# goofylite.net
KiCad netlist of a schematic drawn in EAGLE
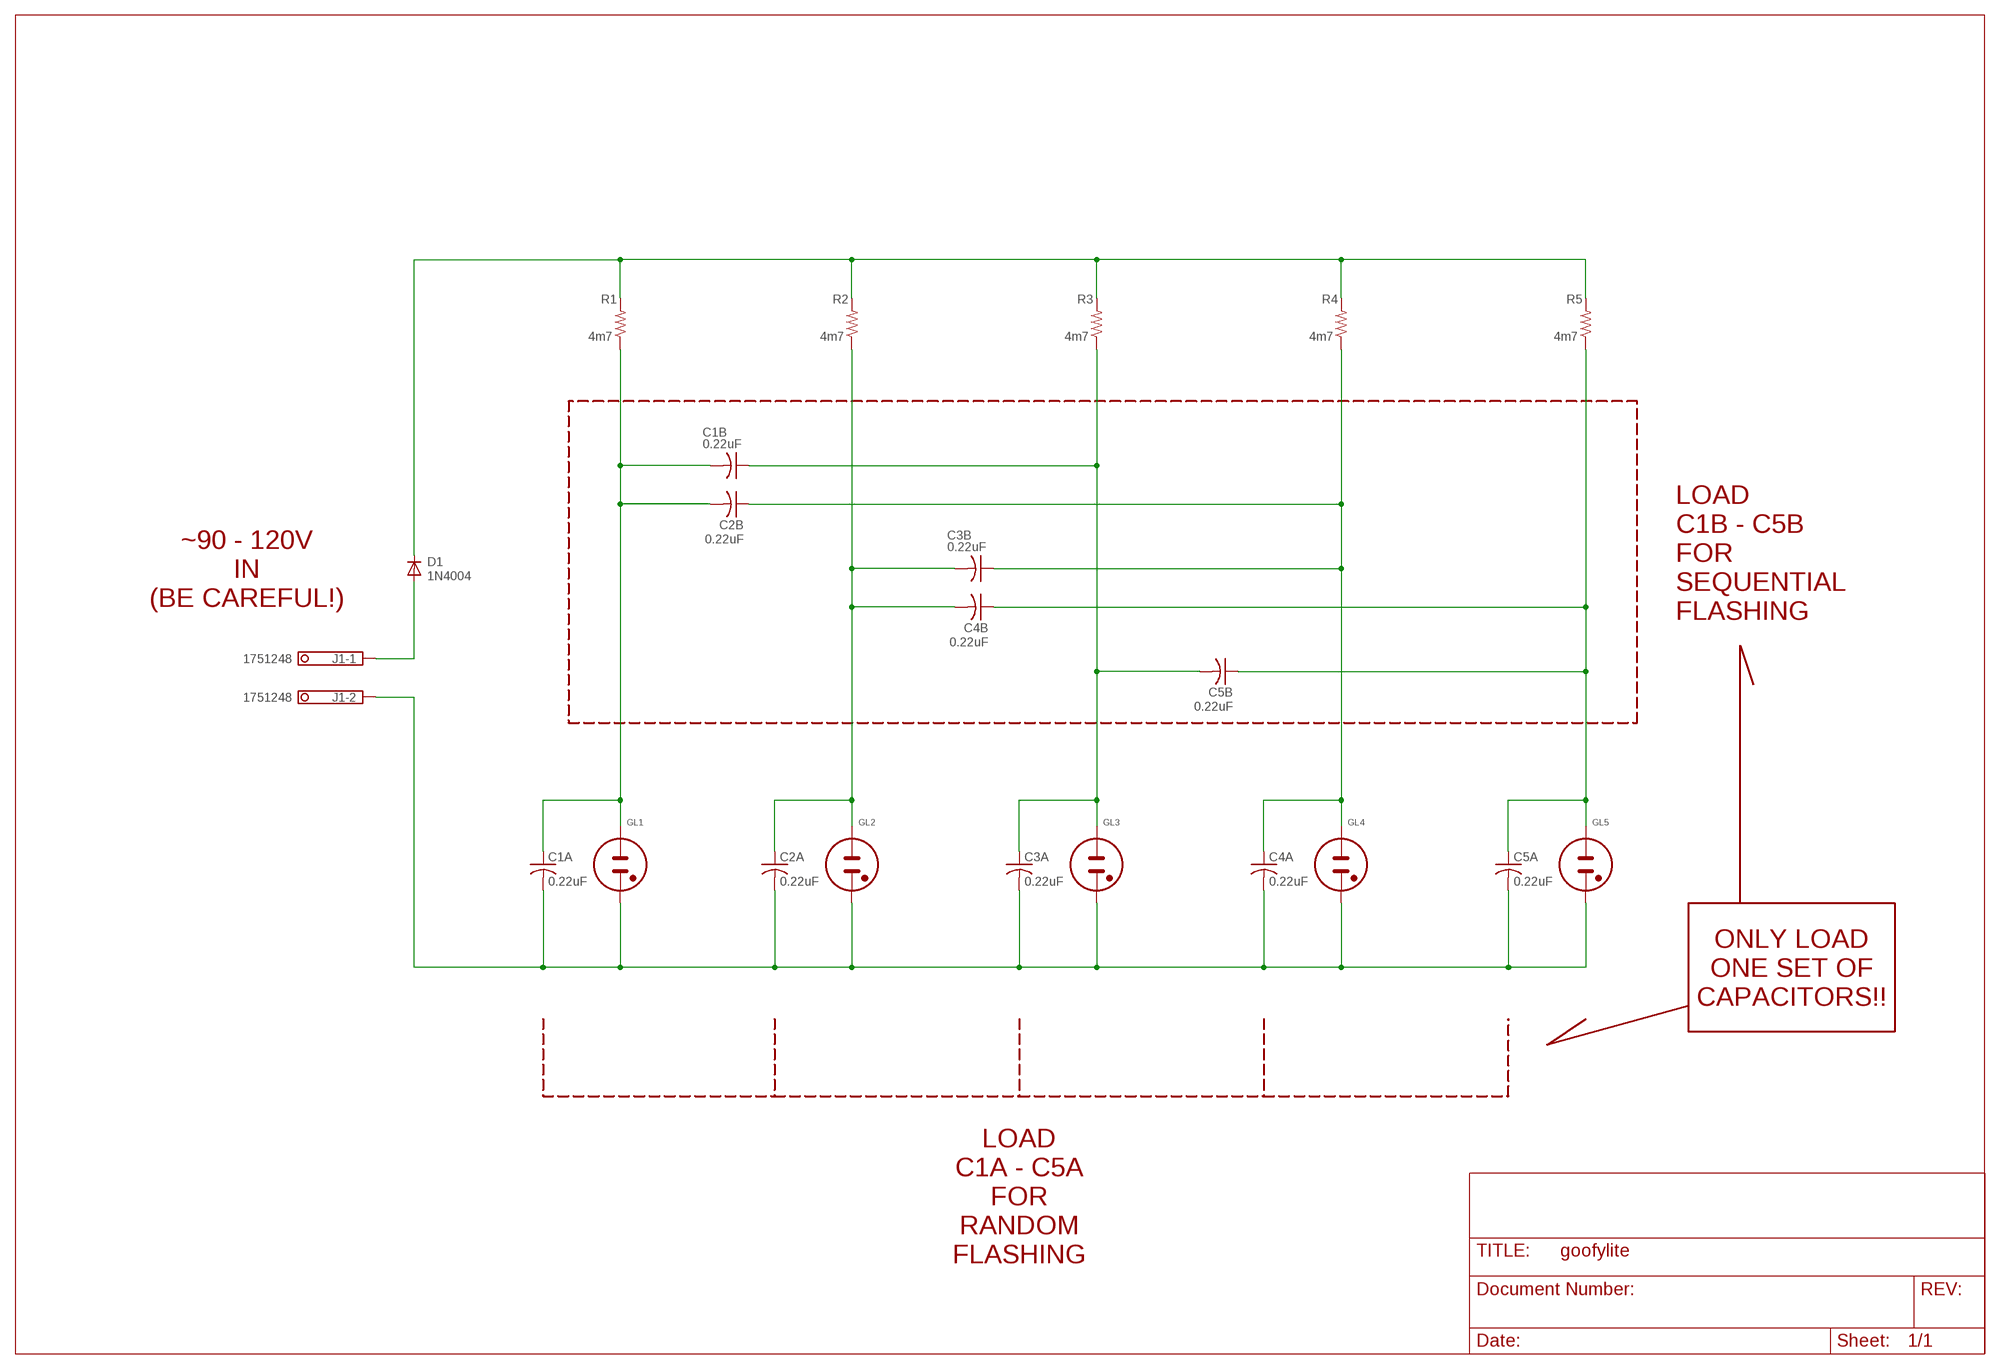
[diagram p0: schematic, sheet 1]

(export (version "E")
  (design (tool "Eeschema 10.0.6"))
  (components
    (comp (ref "C1A")
      (value "0.22uF")
      (footprint "eagle-import:C150-054X183")
      (libsource (lib "eagle-import") (part "C-US150-054X183"))
    )
    (comp (ref "C1B")
      (value "0.22uF")
      (footprint "eagle-import:C150-054X183")
      (libsource (lib "eagle-import") (part "C-US150-054X183"))
    )
    (comp (ref "C2A")
      (value "0.22uF")
      (footprint "eagle-import:C150-054X183")
      (libsource (lib "eagle-import") (part "C-US150-054X183"))
    )
    (comp (ref "C2B")
      (value "0.22uF")
      (footprint "eagle-import:C150-054X183")
      (libsource (lib "eagle-import") (part "C-US150-054X183"))
    )
    (comp (ref "C3A")
      (value "0.22uF")
      (footprint "eagle-import:C150-054X183")
      (libsource (lib "eagle-import") (part "C-US150-054X183"))
    )
    (comp (ref "C3B")
      (value "0.22uF")
      (footprint "eagle-import:C150-054X183")
      (libsource (lib "eagle-import") (part "C-US150-054X183"))
    )
    (comp (ref "C4A")
      (value "0.22uF")
      (footprint "eagle-import:C150-054X183")
      (libsource (lib "eagle-import") (part "C-US150-054X183"))
    )
    (comp (ref "C4B")
      (value "0.22uF")
      (footprint "eagle-import:C150-054X183")
      (libsource (lib "eagle-import") (part "C-US150-054X183"))
    )
    (comp (ref "C5A")
      (value "0.22uF")
      (footprint "eagle-import:C150-054X183")
      (libsource (lib "eagle-import") (part "C-US150-054X183"))
    )
    (comp (ref "C5B")
      (value "0.22uF")
      (footprint "eagle-import:C150-054X183")
      (libsource (lib "eagle-import") (part "C-US150-054X183"))
    )
    (comp (ref "D1")
      (value "1N4004")
      (footprint "eagle-import:DO41-10")
      (libsource (lib "eagle-import") (part "1N4004"))
    )
    (comp (ref "GL1")
      (value "NE2-NEON-BULB-DRILL")
      (footprint "eagle-import:NE2-NEON-BULB-DRILL")
      (libsource (lib "eagle-import") (part "NE2-NEON-BULB-DRILL"))
    )
    (comp (ref "GL2")
      (value "NE2-NEON-BULB-DRILL")
      (footprint "eagle-import:NE2-NEON-BULB-DRILL")
      (libsource (lib "eagle-import") (part "NE2-NEON-BULB-DRILL"))
    )
    (comp (ref "GL3")
      (value "NE2-NEON-BULB-DRILL")
      (footprint "eagle-import:NE2-NEON-BULB-DRILL")
      (libsource (lib "eagle-import") (part "NE2-NEON-BULB-DRILL"))
    )
    (comp (ref "GL4")
      (value "NE2-NEON-BULB-DRILL")
      (footprint "eagle-import:NE2-NEON-BULB-DRILL")
      (libsource (lib "eagle-import") (part "NE2-NEON-BULB-DRILL"))
    )
    (comp (ref "GL5")
      (value "NE2-NEON-BULB-DRILL")
      (footprint "eagle-import:NE2-NEON-BULB-DRILL")
      (libsource (lib "eagle-import") (part "NE2-NEON-BULB-DRILL"))
    )
    (comp (ref "J1")
      (value "1751248")
      (footprint "eagle-import:1751248")
      (libsource (lib "eagle-import") (part "1751248"))
    )
    (comp (ref "R1")
      (value "4m7")
      (footprint "eagle-import:0204_7")
      (libsource (lib "eagle-import") (part "R-US_0204/7"))
    )
    (comp (ref "R2")
      (value "4m7")
      (footprint "eagle-import:0204_7")
      (libsource (lib "eagle-import") (part "R-US_0204/7"))
    )
    (comp (ref "R3")
      (value "4m7")
      (footprint "eagle-import:0204_7")
      (libsource (lib "eagle-import") (part "R-US_0204/7"))
    )
    (comp (ref "R4")
      (value "4m7")
      (footprint "eagle-import:0204_7")
      (libsource (lib "eagle-import") (part "R-US_0204/7"))
    )
    (comp (ref "R5")
      (value "4m7")
      (footprint "eagle-import:0204_7")
      (libsource (lib "eagle-import") (part "R-US_0204/7"))
    )
  )
  (nets
    (net (code "1") (name "Net-(D1-PadC)") (class "Default")
      (node (ref "D1") (pin "C") (pinfunction "C_C") (pintype "passive"))
      (node (ref "R1") (pin "2") (pinfunction "2_2") (pintype "passive"))
      (node (ref "R2") (pin "2") (pinfunction "2_2") (pintype "passive"))
      (node (ref "R3") (pin "2") (pinfunction "2_2") (pintype "passive"))
      (node (ref "R4") (pin "2") (pinfunction "2_2") (pintype "passive"))
      (node (ref "R5") (pin "2") (pinfunction "2_2") (pintype "passive"))
    )
    (net (code "2") (name "Net-(GL1-A)") (class "Default")
      (node (ref "C1A") (pin "1") (pinfunction "1_1") (pintype "passive"))
      (node (ref "C1B") (pin "2") (pinfunction "2_2") (pintype "passive"))
      (node (ref "C2B") (pin "2") (pinfunction "2_2") (pintype "passive"))
      (node (ref "GL1") (pin "1") (pinfunction "A_1") (pintype "passive"))
      (node (ref "R1") (pin "1") (pinfunction "1_1") (pintype "passive"))
    )
    (net (code "3") (name "Net-(GL1-A1)") (class "Default")
      (node (ref "C1A") (pin "2") (pinfunction "2_2") (pintype "passive"))
      (node (ref "C2A") (pin "2") (pinfunction "2_2") (pintype "passive"))
      (node (ref "C3A") (pin "2") (pinfunction "2_2") (pintype "passive"))
      (node (ref "C4A") (pin "2") (pinfunction "2_2") (pintype "passive"))
      (node (ref "C5A") (pin "2") (pinfunction "2_2") (pintype "passive"))
      (node (ref "GL1") (pin "2") (pinfunction "A1_2") (pintype "passive"))
      (node (ref "GL2") (pin "2") (pinfunction "A1_2") (pintype "passive"))
      (node (ref "GL3") (pin "2") (pinfunction "A1_2") (pintype "passive"))
      (node (ref "GL4") (pin "2") (pinfunction "A1_2") (pintype "passive"))
      (node (ref "GL5") (pin "2") (pinfunction "A1_2") (pintype "passive"))
      (node (ref "J1") (pin "2") (pinfunction "K_2") (pintype "passive"))
    )
    (net (code "4") (name "Net-(GL2-A)") (class "Default")
      (node (ref "C2A") (pin "1") (pinfunction "1_1") (pintype "passive"))
      (node (ref "C3B") (pin "2") (pinfunction "2_2") (pintype "passive"))
      (node (ref "C4B") (pin "2") (pinfunction "2_2") (pintype "passive"))
      (node (ref "GL2") (pin "1") (pinfunction "A_1") (pintype "passive"))
      (node (ref "R2") (pin "1") (pinfunction "1_1") (pintype "passive"))
    )
    (net (code "5") (name "Net-(GL3-A)") (class "Default")
      (node (ref "C1B") (pin "1") (pinfunction "1_1") (pintype "passive"))
      (node (ref "C3A") (pin "1") (pinfunction "1_1") (pintype "passive"))
      (node (ref "C5B") (pin "2") (pinfunction "2_2") (pintype "passive"))
      (node (ref "GL3") (pin "1") (pinfunction "A_1") (pintype "passive"))
      (node (ref "R3") (pin "1") (pinfunction "1_1") (pintype "passive"))
    )
    (net (code "6") (name "Net-(GL4-A)") (class "Default")
      (node (ref "C2B") (pin "1") (pinfunction "1_1") (pintype "passive"))
      (node (ref "C3B") (pin "1") (pinfunction "1_1") (pintype "passive"))
      (node (ref "C4A") (pin "1") (pinfunction "1_1") (pintype "passive"))
      (node (ref "GL4") (pin "1") (pinfunction "A_1") (pintype "passive"))
      (node (ref "R4") (pin "1") (pinfunction "1_1") (pintype "passive"))
    )
    (net (code "7") (name "Net-(GL5-A)") (class "Default")
      (node (ref "C4B") (pin "1") (pinfunction "1_1") (pintype "passive"))
      (node (ref "C5A") (pin "1") (pinfunction "1_1") (pintype "passive"))
      (node (ref "C5B") (pin "1") (pinfunction "1_1") (pintype "passive"))
      (node (ref "GL5") (pin "1") (pinfunction "A_1") (pintype "passive"))
      (node (ref "R5") (pin "1") (pinfunction "1_1") (pintype "passive"))
    )
    (net (code "8") (name "Net-(J1A-K)") (class "Default")
      (node (ref "D1") (pin "A") (pinfunction "A_A") (pintype "passive"))
      (node (ref "J1") (pin "1") (pinfunction "K_1") (pintype "passive"))
    )
  )
)
